# ATtiny4313_PN532.net
KiCad netlist of a schematic drawn in EAGLE
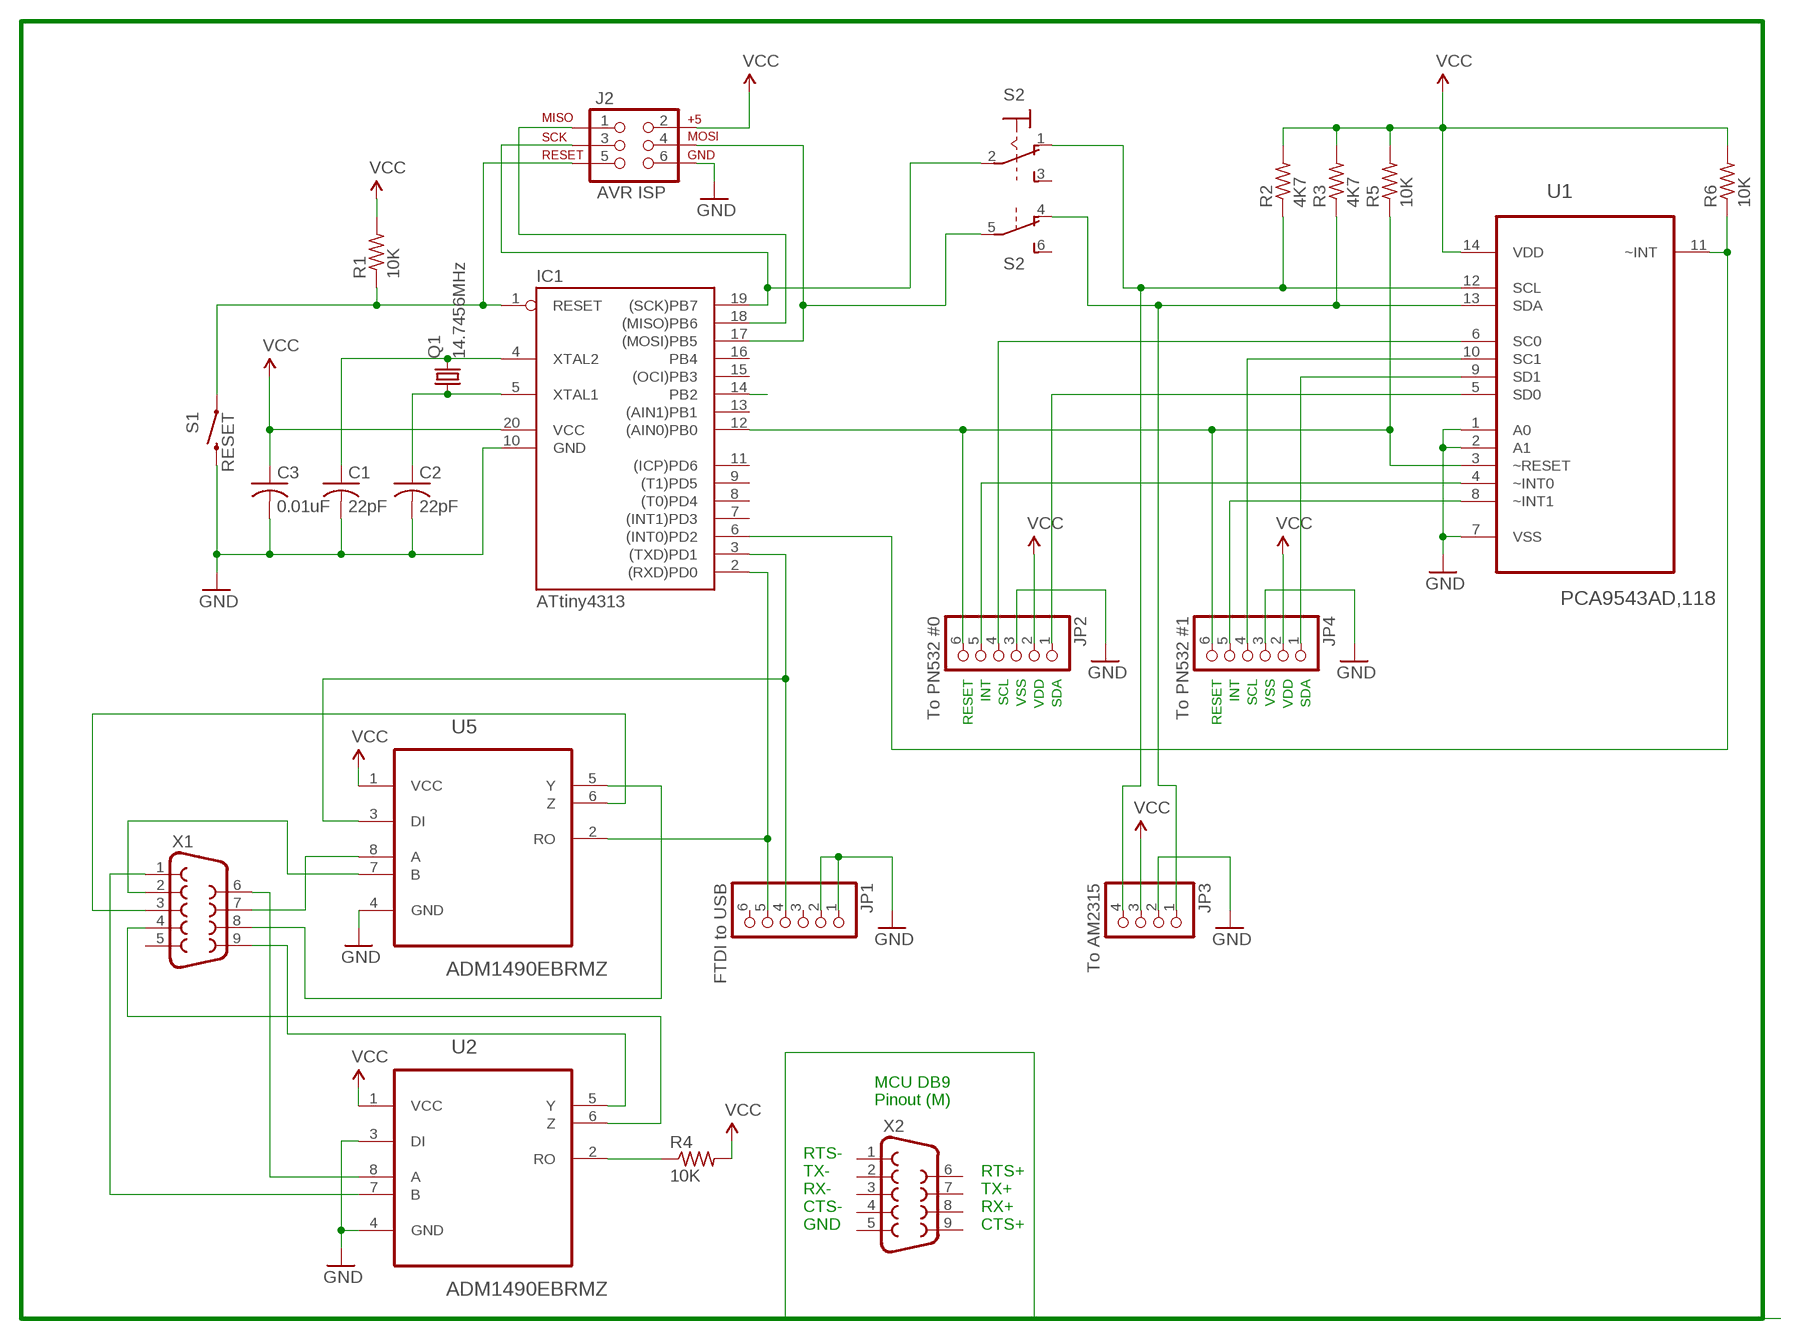
[diagram p0: schematic, sheet 1]

(export (version "E")
  (design (tool "Eeschema 10.0.6"))
  (components
    (comp (ref "C1")
      (value "22pF")
      (footprint "eagle-import:C025-024X044")
      (libsource (lib "eagle-import") (part "C-US025-024X044"))
    )
    (comp (ref "C2")
      (value "22pF")
      (footprint "eagle-import:C025-024X044")
      (libsource (lib "eagle-import") (part "C-US025-024X044"))
    )
    (comp (ref "C3")
      (value "0.01uF")
      (footprint "eagle-import:C025-024X044")
      (libsource (lib "eagle-import") (part "C-US025-024X044"))
    )
    (comp (ref "IC1")
      (value "ATtiny4313")
      (footprint "eagle-import:DIL20")
      (libsource (lib "eagle-import") (part "AT90S2313P"))
    )
    (comp (ref "J2")
      (value "AVR ISP")
      (footprint "eagle-import:2X3")
      (libsource (lib "eagle-import") (part "AVR_SPI_PRG_6PTH"))
    )
    (comp (ref "JP1")
      (value "FTDI to USB")
      (footprint "eagle-import:1X06_90")
      (libsource (lib "eagle-import") (part "PINHD-1X6/90"))
    )
    (comp (ref "JP2")
      (value "To PN532 #0")
      (footprint "eagle-import:1X06_90")
      (libsource (lib "eagle-import") (part "PINHD-1X6/90"))
    )
    (comp (ref "JP3")
      (value "To AM2315")
      (footprint "eagle-import:1X04_90")
      (libsource (lib "eagle-import") (part "PINHD-1X4/90"))
    )
    (comp (ref "JP4")
      (value "To PN532 #1")
      (footprint "eagle-import:1X06_90")
      (libsource (lib "eagle-import") (part "PINHD-1X6/90"))
    )
    (comp (ref "Q1")
      (value "14.7456MHz")
      (footprint "eagle-import:HC49U-V")
      (libsource (lib "eagle-import") (part "CRYSTALHC49U-V"))
    )
    (comp (ref "R1")
      (value "10K")
      (footprint "eagle-import:0204V")
      (libsource (lib "eagle-import") (part "R-US_0204/2V"))
    )
    (comp (ref "R2")
      (value "4K7")
      (footprint "eagle-import:0204V")
      (libsource (lib "eagle-import") (part "R-US_0204/2V"))
    )
    (comp (ref "R3")
      (value "4K7")
      (footprint "eagle-import:0204V")
      (libsource (lib "eagle-import") (part "R-US_0204/2V"))
    )
    (comp (ref "R4")
      (value "10K")
      (footprint "eagle-import:0204V")
      (libsource (lib "eagle-import") (part "R-US_0204/2V"))
    )
    (comp (ref "R5")
      (value "10K")
      (footprint "eagle-import:0204V")
      (libsource (lib "eagle-import") (part "R-US_0204/2V"))
    )
    (comp (ref "R6")
      (value "10K")
      (footprint "eagle-import:0204V")
      (libsource (lib "eagle-import") (part "R-US_0204/2V"))
    )
    (comp (ref "S1")
      (value "RESET")
      (footprint "eagle-import:TACTILE-PTH")
      (libsource (lib "eagle-import") (part "SWITCH-MOMENTARY-2PTH"))
    )
    (comp (ref "S2")
      (value "320-938")
      (footprint "eagle-import:320-938")
      (libsource (lib "eagle-import") (part "320-938"))
    )
    (comp (ref "U1")
      (value "PCA9543AD,118")
      (footprint "eagle-import:SOIC127P600X175-14N")
      (libsource (lib "eagle-import") (part "PCA9543AD,118"))
    )
    (comp (ref "U2")
      (value "ADM1490EBRMZ")
      (footprint "eagle-import:SOP65P490X110-8N")
      (libsource (lib "eagle-import") (part "ADM1490EBRMZ"))
    )
    (comp (ref "U5")
      (value "ADM1490EBRMZ")
      (footprint "eagle-import:SOP65P490X110-8N")
      (libsource (lib "eagle-import") (part "ADM1490EBRMZ"))
    )
    (comp (ref "X1")
      (value "DB9MALE")
      (footprint "eagle-import:DB9_MALE")
      (libsource (lib "eagle-import") (part "DB9MALE"))
    )
    (comp (ref "X2")
      (value "DB9MALE")
      (footprint "eagle-import:DB9_MALE")
      (libsource (lib "eagle-import") (part "DB9MALE"))
    )
  )
  (nets
    (net (code "1") (name "GND") (class "Default")
      (node (ref "C1") (pin "2") (pinfunction "2_2") (pintype "passive"))
      (node (ref "C2") (pin "2") (pinfunction "2_2") (pintype "passive"))
      (node (ref "C3") (pin "2") (pinfunction "2_2") (pintype "passive"))
      (node (ref "IC1") (pin "10") (pinfunction "GND_10") (pintype "power_in"))
      (node (ref "J2") (pin "6") (pinfunction "6_6") (pintype "passive"))
      (node (ref "JP1") (pin "1") (pinfunction "1_1") (pintype "passive"))
      (node (ref "JP1") (pin "2") (pinfunction "2_2") (pintype "passive"))
      (node (ref "JP2") (pin "3") (pinfunction "3_3") (pintype "passive"))
      (node (ref "JP3") (pin "2") (pinfunction "2_2") (pintype "passive"))
      (node (ref "JP4") (pin "3") (pinfunction "3_3") (pintype "passive"))
      (node (ref "S1") (pin "3") (pinfunction "2_3") (pintype "passive"))
      (node (ref "U1") (pin "1") (pinfunction "A0_1") (pintype "input"))
      (node (ref "U1") (pin "2") (pinfunction "A1_2") (pintype "input"))
      (node (ref "U1") (pin "7") (pinfunction "VSS_7") (pintype "passive"))
      (node (ref "U2") (pin "3") (pinfunction "DI_3") (pintype "input"))
      (node (ref "U2") (pin "4") (pinfunction "GND_4") (pintype "passive"))
      (node (ref "U5") (pin "4") (pinfunction "GND_4") (pintype "passive"))
    )
    (net (code "2") (name "Net-(IC1-(AIN0)PB0)") (class "Default")
      (node (ref "IC1") (pin "12") (pinfunction "(AIN0)PB0_12") (pintype "bidirectional"))
      (node (ref "JP2") (pin "6") (pinfunction "6_6") (pintype "passive"))
      (node (ref "JP4") (pin "6") (pinfunction "6_6") (pintype "passive"))
      (node (ref "R5") (pin "1") (pinfunction "1_1") (pintype "passive"))
      (node (ref "U1") (pin "3") (pinfunction "~{RESET}_3") (pintype "input"))
    )
    (net (code "3") (name "Net-(IC1-(INT0)PD2)") (class "Default")
      (node (ref "IC1") (pin "6") (pinfunction "(INT0)PD2_6") (pintype "bidirectional"))
      (node (ref "R6") (pin "1") (pinfunction "1_1") (pintype "passive"))
      (node (ref "U1") (pin "11") (pinfunction "~{INT}_11") (pintype "output"))
    )
    (net (code "4") (name "Net-(IC1-(MISO)PB6)") (class "Default")
      (node (ref "IC1") (pin "18") (pinfunction "(MISO)PB6_18") (pintype "bidirectional"))
      (node (ref "J2") (pin "1") (pinfunction "1_1") (pintype "passive"))
    )
    (net (code "5") (name "Net-(IC1-(MOSI)PB5)") (class "Default")
      (node (ref "IC1") (pin "17") (pinfunction "(MOSI)PB5_17") (pintype "bidirectional"))
      (node (ref "J2") (pin "4") (pinfunction "4_4") (pintype "passive"))
      (node (ref "S2") (pin "5") (pinfunction "P_5") (pintype "passive"))
    )
    (net (code "6") (name "Net-(IC1-(RXD)PD0)") (class "Default")
      (node (ref "IC1") (pin "2") (pinfunction "(RXD)PD0_2") (pintype "bidirectional"))
      (node (ref "JP1") (pin "5") (pinfunction "5_5") (pintype "passive"))
      (node (ref "U5") (pin "2") (pinfunction "RO_2") (pintype "output"))
    )
    (net (code "7") (name "Net-(IC1-(SCK)PB7)") (class "Default")
      (node (ref "IC1") (pin "19") (pinfunction "(SCK)PB7_19") (pintype "bidirectional"))
      (node (ref "J2") (pin "3") (pinfunction "3_3") (pintype "passive"))
      (node (ref "S2") (pin "2") (pinfunction "P_2") (pintype "passive"))
    )
    (net (code "8") (name "Net-(IC1-(TXD)PD1)") (class "Default")
      (node (ref "IC1") (pin "3") (pinfunction "(TXD)PD1_3") (pintype "bidirectional"))
      (node (ref "JP1") (pin "4") (pinfunction "4_4") (pintype "passive"))
      (node (ref "U5") (pin "3") (pinfunction "DI_3") (pintype "input"))
    )
    (net (code "9") (name "Net-(IC1-RESET)") (class "Default")
      (node (ref "IC1") (pin "1") (pinfunction "RESET_1") (pintype "bidirectional"))
      (node (ref "J2") (pin "5") (pinfunction "5_5") (pintype "passive"))
      (node (ref "R1") (pin "1") (pinfunction "1_1") (pintype "passive"))
      (node (ref "S1") (pin "1") (pinfunction "1_1") (pintype "passive"))
    )
    (net (code "10") (name "Net-(IC1-XTAL1)") (class "Default")
      (node (ref "C2") (pin "1") (pinfunction "1_1") (pintype "passive"))
      (node (ref "IC1") (pin "5") (pinfunction "XTAL1_5") (pintype "bidirectional"))
      (node (ref "Q1") (pin "1") (pinfunction "1_1") (pintype "passive"))
    )
    (net (code "11") (name "Net-(IC1-XTAL2)") (class "Default")
      (node (ref "C1") (pin "1") (pinfunction "1_1") (pintype "passive"))
      (node (ref "IC1") (pin "4") (pinfunction "XTAL2_4") (pintype "bidirectional"))
      (node (ref "Q1") (pin "2") (pinfunction "2_2") (pintype "passive"))
    )
    (net (code "12") (name "Net-(S2A-O)") (class "Default")
      (node (ref "JP3") (pin "4") (pinfunction "4_4") (pintype "passive"))
      (node (ref "R2") (pin "1") (pinfunction "1_1") (pintype "passive"))
      (node (ref "S2") (pin "1") (pinfunction "O_1") (pintype "passive"))
      (node (ref "U1") (pin "12") (pinfunction "SCL_12") (pintype "bidirectional"))
    )
    (net (code "13") (name "Net-(S2B-O)") (class "Default")
      (node (ref "JP3") (pin "1") (pinfunction "1_1") (pintype "passive"))
      (node (ref "R3") (pin "1") (pinfunction "1_1") (pintype "passive"))
      (node (ref "S2") (pin "4") (pinfunction "O_4") (pintype "passive"))
      (node (ref "U1") (pin "13") (pinfunction "SDA_13") (pintype "bidirectional"))
    )
    (net (code "14") (name "Net-(U1-SC0)") (class "Default")
      (node (ref "JP2") (pin "4") (pinfunction "4_4") (pintype "passive"))
      (node (ref "U1") (pin "6") (pinfunction "SC0_6") (pintype "input"))
    )
    (net (code "15") (name "Net-(U1-SC1)") (class "Default")
      (node (ref "JP4") (pin "4") (pinfunction "4_4") (pintype "passive"))
      (node (ref "U1") (pin "10") (pinfunction "SC1_10") (pintype "input"))
    )
    (net (code "16") (name "Net-(U1-SD0)") (class "Default")
      (node (ref "JP2") (pin "1") (pinfunction "1_1") (pintype "passive"))
      (node (ref "U1") (pin "5") (pinfunction "SD0_5") (pintype "input"))
    )
    (net (code "17") (name "Net-(U1-SD1)") (class "Default")
      (node (ref "JP4") (pin "1") (pinfunction "1_1") (pintype "passive"))
      (node (ref "U1") (pin "9") (pinfunction "SD1_9") (pintype "input"))
    )
    (net (code "18") (name "Net-(U1-~{INT0})") (class "Default")
      (node (ref "JP2") (pin "5") (pinfunction "5_5") (pintype "passive"))
      (node (ref "U1") (pin "4") (pinfunction "~{INT0}_4") (pintype "input"))
    )
    (net (code "19") (name "Net-(U1-~{INT1})") (class "Default")
      (node (ref "JP4") (pin "5") (pinfunction "5_5") (pintype "passive"))
      (node (ref "U1") (pin "8") (pinfunction "~{INT1}_8") (pintype "input"))
    )
    (net (code "20") (name "Net-(U2-A)") (class "Default")
      (node (ref "U2") (pin "8") (pinfunction "A_8") (pintype "input"))
      (node (ref "X1") (pin "6") (pinfunction "6_6") (pintype "passive"))
    )
    (net (code "21") (name "Net-(U2-B)") (class "Default")
      (node (ref "U2") (pin "7") (pinfunction "B_7") (pintype "input"))
      (node (ref "X1") (pin "1") (pinfunction "1_1") (pintype "passive"))
    )
    (net (code "22") (name "Net-(U2-RO)") (class "Default")
      (node (ref "R4") (pin "1") (pinfunction "1_1") (pintype "passive"))
      (node (ref "U2") (pin "2") (pinfunction "RO_2") (pintype "output"))
    )
    (net (code "23") (name "Net-(U2-Y)") (class "Default")
      (node (ref "U2") (pin "5") (pinfunction "Y_5") (pintype "output"))
      (node (ref "X1") (pin "9") (pinfunction "9_9") (pintype "passive"))
    )
    (net (code "24") (name "Net-(U2-Z)") (class "Default")
      (node (ref "U2") (pin "6") (pinfunction "Z_6") (pintype "output"))
      (node (ref "X1") (pin "4") (pinfunction "4_4") (pintype "passive"))
    )
    (net (code "25") (name "Net-(U5-A)") (class "Default")
      (node (ref "U5") (pin "8") (pinfunction "A_8") (pintype "input"))
      (node (ref "X1") (pin "7") (pinfunction "7_7") (pintype "passive"))
    )
    (net (code "26") (name "Net-(U5-B)") (class "Default")
      (node (ref "U5") (pin "7") (pinfunction "B_7") (pintype "input"))
      (node (ref "X1") (pin "2") (pinfunction "2_2") (pintype "passive"))
    )
    (net (code "27") (name "Net-(U5-Y)") (class "Default")
      (node (ref "U5") (pin "5") (pinfunction "Y_5") (pintype "output"))
      (node (ref "X1") (pin "8") (pinfunction "8_8") (pintype "passive"))
    )
    (net (code "28") (name "Net-(U5-Z)") (class "Default")
      (node (ref "U5") (pin "6") (pinfunction "Z_6") (pintype "output"))
      (node (ref "X1") (pin "3") (pinfunction "3_3") (pintype "passive"))
    )
    (net (code "29") (name "VCC") (class "Default")
      (node (ref "C3") (pin "1") (pinfunction "1_1") (pintype "passive"))
      (node (ref "IC1") (pin "20") (pinfunction "VCC_20") (pintype "power_in"))
      (node (ref "J2") (pin "2") (pinfunction "2_2") (pintype "passive"))
      (node (ref "JP2") (pin "2") (pinfunction "2_2") (pintype "passive"))
      (node (ref "JP3") (pin "3") (pinfunction "3_3") (pintype "passive"))
      (node (ref "JP4") (pin "2") (pinfunction "2_2") (pintype "passive"))
      (node (ref "R1") (pin "2") (pinfunction "2_2") (pintype "passive"))
      (node (ref "R2") (pin "2") (pinfunction "2_2") (pintype "passive"))
      (node (ref "R3") (pin "2") (pinfunction "2_2") (pintype "passive"))
      (node (ref "R4") (pin "2") (pinfunction "2_2") (pintype "passive"))
      (node (ref "R5") (pin "2") (pinfunction "2_2") (pintype "passive"))
      (node (ref "R6") (pin "2") (pinfunction "2_2") (pintype "passive"))
      (node (ref "U1") (pin "14") (pinfunction "VDD_14") (pintype "power_in"))
      (node (ref "U2") (pin "1") (pinfunction "VCC_1") (pintype "power_in"))
      (node (ref "U5") (pin "1") (pinfunction "VCC_1") (pintype "power_in"))
    )
    (net (code "30") (name "unconnected-(IC1-(AIN1)PB1-Pad13)") (class "Default")
      (node (ref "IC1") (pin "13") (pinfunction "(AIN1)PB1_13") (pintype "bidirectional"))
    )
    (net (code "31") (name "unconnected-(IC1-(ICP)PD6-Pad11)") (class "Default")
      (node (ref "IC1") (pin "11") (pinfunction "(ICP)PD6_11") (pintype "bidirectional"))
    )
    (net (code "32") (name "unconnected-(IC1-(INT1)PD3-Pad7)") (class "Default")
      (node (ref "IC1") (pin "7") (pinfunction "(INT1)PD3_7") (pintype "bidirectional"))
    )
    (net (code "33") (name "unconnected-(IC1-(OCI)PB3-Pad15)") (class "Default")
      (node (ref "IC1") (pin "15") (pinfunction "(OCI)PB3_15") (pintype "bidirectional"))
    )
    (net (code "34") (name "unconnected-(IC1-(T0)PD4-Pad8)") (class "Default")
      (node (ref "IC1") (pin "8") (pinfunction "(T0)PD4_8") (pintype "bidirectional"))
    )
    (net (code "35") (name "unconnected-(IC1-(T1)PD5-Pad9)") (class "Default")
      (node (ref "IC1") (pin "9") (pinfunction "(T1)PD5_9") (pintype "bidirectional"))
    )
    (net (code "36") (name "unconnected-(IC1-PB2-Pad14)") (class "Default")
      (node (ref "IC1") (pin "14") (pinfunction "PB2_14") (pintype "bidirectional"))
    )
    (net (code "37") (name "unconnected-(IC1-PB4-Pad16)") (class "Default")
      (node (ref "IC1") (pin "16") (pinfunction "PB4_16") (pintype "bidirectional"))
    )
    (net (code "38") (name "unconnected-(JP1-Pad3)") (class "Default")
      (node (ref "JP1") (pin "3") (pinfunction "3_3") (pintype "passive"))
    )
    (net (code "39") (name "unconnected-(JP1-Pad6)") (class "Default")
      (node (ref "JP1") (pin "6") (pinfunction "6_6") (pintype "passive"))
    )
    (net (code "40") (name "unconnected-(S2A-S-Pad3)") (class "Default")
      (node (ref "S2") (pin "3") (pinfunction "S_3") (pintype "passive"))
    )
    (net (code "41") (name "unconnected-(S2B-S-Pad6)") (class "Default")
      (node (ref "S2") (pin "6") (pinfunction "S_6") (pintype "passive"))
    )
    (net (code "42") (name "unconnected-(X1-Pad5)") (class "Default")
      (node (ref "X1") (pin "5") (pinfunction "5_5") (pintype "passive"))
    )
    (net (code "43") (name "unconnected-(X2-Pad1)") (class "Default")
      (node (ref "X2") (pin "1") (pinfunction "1_1") (pintype "passive"))
    )
    (net (code "44") (name "unconnected-(X2-Pad2)") (class "Default")
      (node (ref "X2") (pin "2") (pinfunction "2_2") (pintype "passive"))
    )
    (net (code "45") (name "unconnected-(X2-Pad3)") (class "Default")
      (node (ref "X2") (pin "3") (pinfunction "3_3") (pintype "passive"))
    )
    (net (code "46") (name "unconnected-(X2-Pad4)") (class "Default")
      (node (ref "X2") (pin "4") (pinfunction "4_4") (pintype "passive"))
    )
    (net (code "47") (name "unconnected-(X2-Pad5)") (class "Default")
      (node (ref "X2") (pin "5") (pinfunction "5_5") (pintype "passive"))
    )
    (net (code "48") (name "unconnected-(X2-Pad6)") (class "Default")
      (node (ref "X2") (pin "6") (pinfunction "6_6") (pintype "passive"))
    )
    (net (code "49") (name "unconnected-(X2-Pad7)") (class "Default")
      (node (ref "X2") (pin "7") (pinfunction "7_7") (pintype "passive"))
    )
    (net (code "50") (name "unconnected-(X2-Pad8)") (class "Default")
      (node (ref "X2") (pin "8") (pinfunction "8_8") (pintype "passive"))
    )
    (net (code "51") (name "unconnected-(X2-Pad9)") (class "Default")
      (node (ref "X2") (pin "9") (pinfunction "9_9") (pintype "passive"))
    )
  )
)
